# Antenna_Board_v5_0.net
KiCad netlist of a schematic drawn in EAGLE
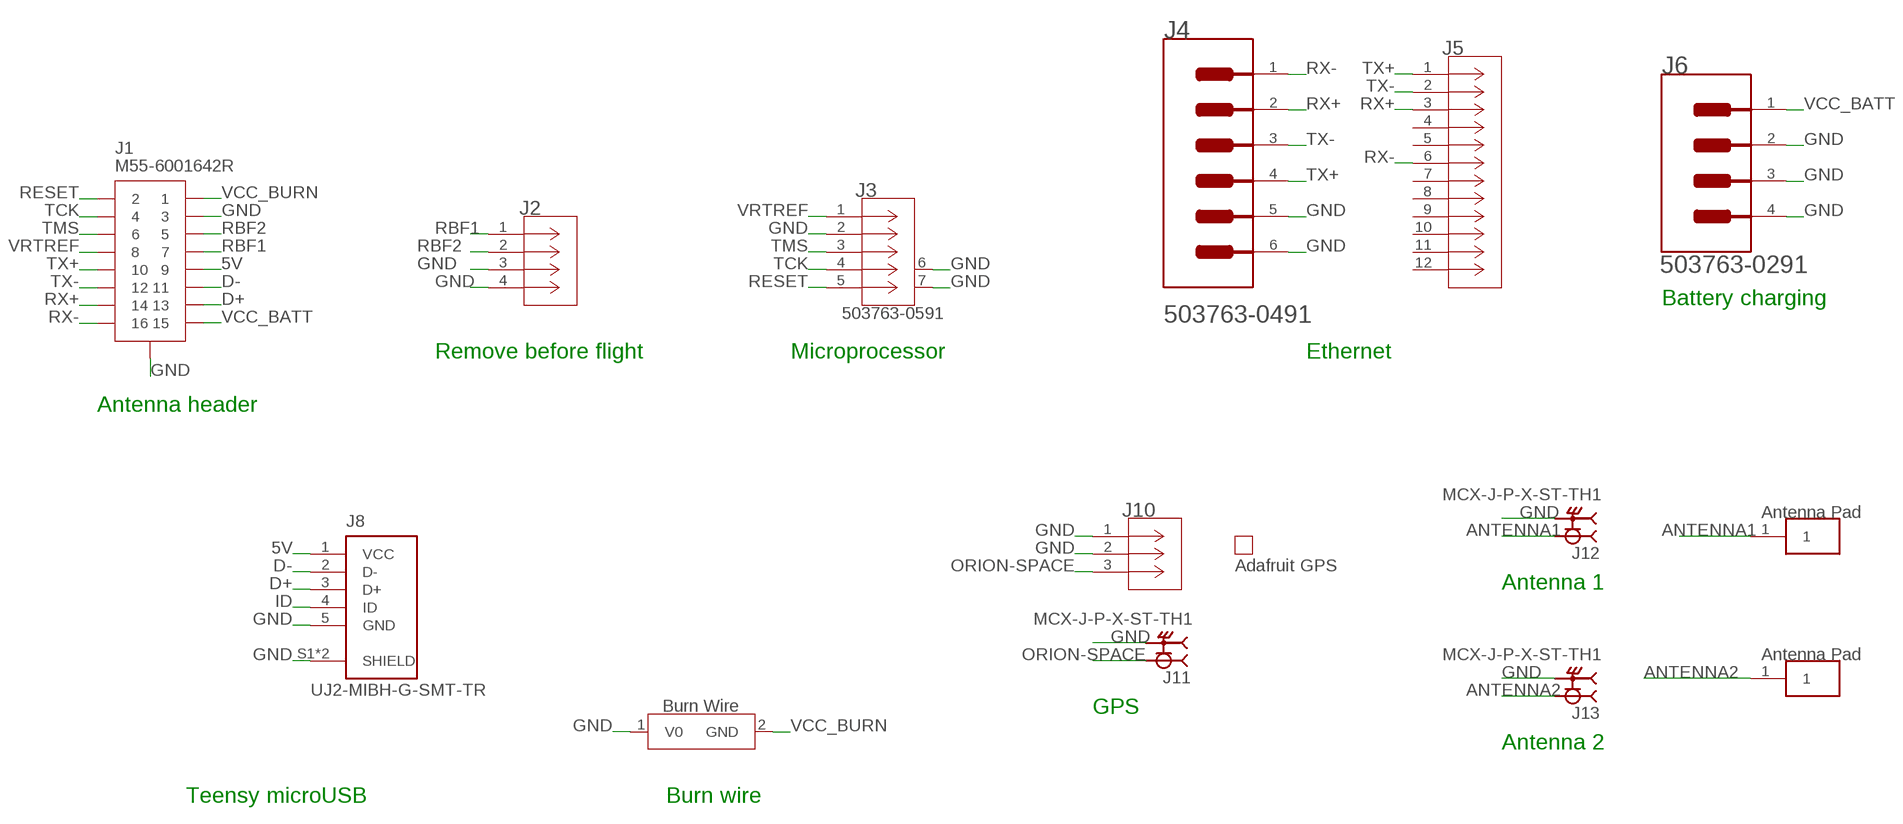
[diagram p0: schematic, sheet 1]

(export (version "E")
  (design (tool "Eeschema 10.0.6"))
  (components
    (comp (ref "GPS")
      (value "PA1010D")
      (footprint "eagle-import:PA1010D")
      (libsource (lib "eagle-import") (part "PA1010D"))
    )
    (comp (ref "J1")
      (value "M55-6001642R")
      (footprint "eagle-import:CONN_M55-6001642R_HRW")
      (fields (field (name "COPYRIGHT") "Copyright (C) 2021 Ultra Librarian. All rights reserved."))
      (libsource (lib "eagle-import") (part "M55-6001642R"))
    )
    (comp (ref "J2")
      (value "5037630291")
      (footprint "eagle-import:CON_5037630291")
      (fields (field (name "COPYRIGHT") "Copyright (C) 2018 Accelerated Designs. All rights reserved"))
      (libsource (lib "eagle-import") (part "5037630291"))
    )
    (comp (ref "J3")
      (value "503763-0591")
      (footprint "eagle-import:CONN_5037630591_MOL")
      (fields (field (name "COPYRIGHT") "Copyright (C) 2018 Accelerated Designs. All rights reserved"))
      (libsource (lib "eagle-import") (part "503763-0591"))
    )
    (comp (ref "J4")
      (value "MOLEX_503763-0491MOLEX_503763-0491_0_0")
      (footprint "eagle-import:MOLEX_503763-0491_0")
      (fields
        (field (name "DIGIKEY_PART_NUMBER") "WM10655CT-ND")
        (field (name "MF") "Molex")
        (field (name "MOUSER_PART_NUMBER") "538-503763-0491")
      )
      (libsource (lib "eagle-import") (part "MOLEX_503763-0491MOLEX_503763-0491_0_0"))
    )
    (comp (ref "J5")
      (value "ARJM11C7-104-AB-EW2")
      (footprint "eagle-import:CONN_EW_ABR")
      (libsource (lib "eagle-import") (part "ARJM11C7-104-AB-EW2"))
    )
    (comp (ref "J6")
      (value "MOLEX_503763-0291MOLEX_503763-0291_0_0")
      (footprint "eagle-import:MOLEX_503763-0291_0")
      (fields
        (field (name "DIGIKEY_PART_NUMBER") "WM10654CT-ND")
        (field (name "MF") "Molex")
        (field (name "MOUSER_PART_NUMBER") "538-503763-0291")
      )
      (libsource (lib "eagle-import") (part "MOLEX_503763-0291MOLEX_503763-0291_0_0"))
    )
    (comp (ref "J8")
      (value "UJ2-MIBH-G-SMT-TR")
      (footprint "eagle-import:CUI_UJ2-MIBH-G-SMT-TR")
      (fields
        (field (name "DIGI-KEY_PART_NUMBER") "2223-UJ2-MIBH-G-SMT-TRCT-ND")
        (field (name "MF") "CUI Devices")
      )
      (libsource (lib "eagle-import") (part "UJ2-MIBH-G-SMT-TR"))
    )
    (comp (ref "J10")
      (value "U.FL-R-SMT-1(01)")
      (footprint "eagle-import:CONN_-SMT-1(01)")
      (fields (field (name "COPYRIGHT") "Copyright (C) 2018 Accelerated Designs. All rights reserved"))
      (libsource (lib "eagle-import") (part "U.FL-R-SMT-1(01)"))
    )
    (comp (ref "J11")
      (value "MCX-J-P-X-ST-TH1")
      (footprint "eagle-import:SAMTEC_MCX-J-P-X-ST-TH1")
      (fields
        (field (name "DIGI-KEY_PART_NUMBER") "SAM8944-ND")
        (field (name "MF") "Samtec")
        (field (name "MP") "MCX-J-P-H-ST-TH1")
      )
      (libsource (lib "eagle-import") (part "MCX-J-P-X-ST-TH1"))
    )
    (comp (ref "J12")
      (value "MCX-J-P-X-ST-TH1")
      (footprint "eagle-import:SAMTEC_MCX-J-P-X-ST-TH1")
      (fields
        (field (name "DIGI-KEY_PART_NUMBER") "SAM8944-ND")
        (field (name "MF") "Samtec")
        (field (name "MP") "MCX-J-P-H-ST-TH1")
      )
      (libsource (lib "eagle-import") (part "MCX-J-P-X-ST-TH1"))
    )
    (comp (ref "J13")
      (value "MCX-J-P-X-ST-TH1")
      (footprint "eagle-import:SAMTEC_MCX-J-P-X-ST-TH1")
      (fields
        (field (name "DIGI-KEY_PART_NUMBER") "SAM8944-ND")
        (field (name "MF") "Samtec")
        (field (name "MP") "MCX-J-P-H-ST-TH1")
      )
      (libsource (lib "eagle-import") (part "MCX-J-P-X-ST-TH1"))
    )
    (comp (ref "U$1")
      (value "ANTENNA_PAD")
      (footprint "eagle-import:ANTENNA_PAD")
      (libsource (lib "eagle-import") (part "ANTENNA_PAD"))
    )
    (comp (ref "U$2")
      (value "ANTENNA_PAD")
      (footprint "eagle-import:ANTENNA_PAD")
      (libsource (lib "eagle-import") (part "ANTENNA_PAD"))
    )
    (comp (ref "U$3")
      (value "BURNWIRE")
      (footprint "eagle-import:BURNWIRE")
      (libsource (lib "eagle-import") (part "BURNWIRE"))
    )
  )
  (nets
    (net (code "1") (name "/5V") (class "Default")
      (node (ref "J1") (pin "9") (pinfunction "9_9") (pintype "passive"))
      (node (ref "J8") (pin "1") (pinfunction "VCC_1") (pintype "power_in"))
    )
    (net (code "2") (name "/ANTENNA1") (class "Default")
      (node (ref "J12") (pin "1") (pinfunction "1_1") (pintype "passive"))
      (node (ref "U$2") (pin "1") (pinfunction "1_1") (pintype "bidirectional"))
    )
    (net (code "3") (name "/ANTENNA2") (class "Default")
      (node (ref "J13") (pin "1") (pinfunction "1_1") (pintype "passive"))
      (node (ref "U$1") (pin "1") (pinfunction "1_1") (pintype "bidirectional"))
    )
    (net (code "4") (name "/D+") (class "Default")
      (node (ref "J1") (pin "13") (pinfunction "13_13") (pintype "passive"))
      (node (ref "J8") (pin "3") (pinfunction "D+_3") (pintype "bidirectional"))
    )
    (net (code "5") (name "/D-") (class "Default")
      (node (ref "J1") (pin "11") (pinfunction "11_11") (pintype "passive"))
      (node (ref "J8") (pin "2") (pinfunction "D-_2") (pintype "bidirectional"))
    )
    (net (code "6") (name "/GND") (class "Default")
      (node (ref "J1") (pin "19") (pinfunction "GND_19") (pintype "passive"))
      (node (ref "J1") (pin "20") (pinfunction "GND_20") (pintype "passive"))
      (node (ref "J1") (pin "21") (pinfunction "GND_21") (pintype "passive"))
      (node (ref "J1") (pin "22") (pinfunction "GND_22") (pintype "passive"))
      (node (ref "J1") (pin "3") (pinfunction "3_3") (pintype "passive"))
      (node (ref "J10") (pin "1") (pinfunction "1_1") (pintype "passive"))
      (node (ref "J10") (pin "2") (pinfunction "2_2") (pintype "passive"))
      (node (ref "J11") (pin "S1") (pinfunction "2_S1") (pintype "passive"))
      (node (ref "J11") (pin "S2") (pinfunction "2_S2") (pintype "passive"))
      (node (ref "J11") (pin "S3") (pinfunction "2_S3") (pintype "passive"))
      (node (ref "J11") (pin "S4") (pinfunction "2_S4") (pintype "passive"))
      (node (ref "J12") (pin "S1") (pinfunction "2_S1") (pintype "passive"))
      (node (ref "J12") (pin "S2") (pinfunction "2_S2") (pintype "passive"))
      (node (ref "J12") (pin "S3") (pinfunction "2_S3") (pintype "passive"))
      (node (ref "J12") (pin "S4") (pinfunction "2_S4") (pintype "passive"))
      (node (ref "J13") (pin "S1") (pinfunction "2_S1") (pintype "passive"))
      (node (ref "J13") (pin "S2") (pinfunction "2_S2") (pintype "passive"))
      (node (ref "J13") (pin "S3") (pinfunction "2_S3") (pintype "passive"))
      (node (ref "J13") (pin "S4") (pinfunction "2_S4") (pintype "passive"))
      (node (ref "J2") (pin "3") (pinfunction "3_3") (pintype "passive"))
      (node (ref "J2") (pin "4") (pinfunction "4_4") (pintype "passive"))
      (node (ref "J3") (pin "2") (pinfunction "2_2") (pintype "passive"))
      (node (ref "J3") (pin "6") (pinfunction "6_6") (pintype "bidirectional"))
      (node (ref "J3") (pin "7") (pinfunction "7_7") (pintype "bidirectional"))
      (node (ref "J4") (pin "5") (pinfunction "MNT_1_5") (pintype "passive"))
      (node (ref "J4") (pin "6") (pinfunction "MNT_2_6") (pintype "passive"))
      (node (ref "J6") (pin "2") (pinfunction "2_2") (pintype "bidirectional"))
      (node (ref "J6") (pin "3") (pinfunction "MNT_1_3") (pintype "bidirectional"))
      (node (ref "J6") (pin "4") (pinfunction "MNT_2_4") (pintype "bidirectional"))
      (node (ref "J8") (pin "5") (pinfunction "GND_5") (pintype "power_in"))
      (node (ref "J8") (pin "S1") (pinfunction "SHIELD_S1") (pintype "passive"))
      (node (ref "J8") (pin "S2") (pinfunction "SHIELD_S2") (pintype "passive"))
      (node (ref "U$3") (pin "1") (pinfunction "V0_1") (pintype "bidirectional"))
    )
    (net (code "7") (name "/ID") (class "Default")
      (node (ref "J8") (pin "4") (pinfunction "ID_4") (pintype "bidirectional"))
    )
    (net (code "8") (name "/ORION-SPACE") (class "Default")
      (node (ref "J10") (pin "3") (pinfunction "3_3") (pintype "passive"))
      (node (ref "J11") (pin "1") (pinfunction "1_1") (pintype "passive"))
    )
    (net (code "9") (name "/RBF1") (class "Default")
      (node (ref "J1") (pin "7") (pinfunction "7_7") (pintype "passive"))
      (node (ref "J2") (pin "1") (pinfunction "1_1") (pintype "passive"))
    )
    (net (code "10") (name "/RBF2") (class "Default")
      (node (ref "J1") (pin "5") (pinfunction "5_5") (pintype "passive"))
      (node (ref "J2") (pin "2") (pinfunction "2_2") (pintype "passive"))
    )
    (net (code "11") (name "/RESET") (class "Default")
      (node (ref "J1") (pin "2") (pinfunction "2_2") (pintype "passive"))
      (node (ref "J3") (pin "5") (pinfunction "5_5") (pintype "passive"))
    )
    (net (code "12") (name "/RX+") (class "Default")
      (node (ref "J1") (pin "14") (pinfunction "14_14") (pintype "passive"))
      (node (ref "J4") (pin "2") (pinfunction "2_2") (pintype "passive"))
      (node (ref "J5") (pin "3") (pinfunction "3_3") (pintype "passive"))
    )
    (net (code "13") (name "/RX-") (class "Default")
      (node (ref "J1") (pin "16") (pinfunction "16_16") (pintype "passive"))
      (node (ref "J4") (pin "1") (pinfunction "1_1") (pintype "passive"))
      (node (ref "J5") (pin "6") (pinfunction "6_6") (pintype "passive"))
    )
    (net (code "14") (name "/TCK") (class "Default")
      (node (ref "J1") (pin "4") (pinfunction "4_4") (pintype "passive"))
      (node (ref "J3") (pin "4") (pinfunction "4_4") (pintype "passive"))
    )
    (net (code "15") (name "/TMS") (class "Default")
      (node (ref "J1") (pin "6") (pinfunction "6_6") (pintype "passive"))
      (node (ref "J3") (pin "3") (pinfunction "3_3") (pintype "passive"))
    )
    (net (code "16") (name "/TX+") (class "Default")
      (node (ref "J1") (pin "10") (pinfunction "10_10") (pintype "passive"))
      (node (ref "J4") (pin "4") (pinfunction "4_4") (pintype "passive"))
      (node (ref "J5") (pin "1") (pinfunction "1_1") (pintype "passive"))
    )
    (net (code "17") (name "/TX-") (class "Default")
      (node (ref "J1") (pin "12") (pinfunction "12_12") (pintype "passive"))
      (node (ref "J4") (pin "3") (pinfunction "3_3") (pintype "passive"))
      (node (ref "J5") (pin "2") (pinfunction "2_2") (pintype "passive"))
    )
    (net (code "18") (name "/VCC_BATT") (class "Default")
      (node (ref "J1") (pin "15") (pinfunction "15_15") (pintype "passive"))
      (node (ref "J6") (pin "1") (pinfunction "1_1") (pintype "bidirectional"))
    )
    (net (code "19") (name "/VCC_BURN") (class "Default")
      (node (ref "J1") (pin "1") (pinfunction "1_1") (pintype "passive"))
      (node (ref "U$3") (pin "2") (pinfunction "GND_2") (pintype "bidirectional"))
    )
    (net (code "20") (name "/VRTREF") (class "Default")
      (node (ref "J1") (pin "8") (pinfunction "8_8") (pintype "passive"))
      (node (ref "J3") (pin "1") (pinfunction "1_1") (pintype "passive"))
    )
    (net (code "21") (name "unconnected-(J5-Pad4)") (class "Default")
      (node (ref "J5") (pin "4") (pinfunction "4_4") (pintype "passive"))
    )
    (net (code "22") (name "unconnected-(J5-Pad5)") (class "Default")
      (node (ref "J5") (pin "5") (pinfunction "5_5") (pintype "passive"))
    )
    (net (code "23") (name "unconnected-(J5-Pad7)") (class "Default")
      (node (ref "J5") (pin "7") (pinfunction "7_7") (pintype "passive"))
    )
    (net (code "24") (name "unconnected-(J5-Pad8)") (class "Default")
      (node (ref "J5") (pin "8") (pinfunction "8_8") (pintype "passive"))
    )
    (net (code "25") (name "unconnected-(J5-Pad9)") (class "Default")
      (node (ref "J5") (pin "9") (pinfunction "9_9") (pintype "passive"))
    )
    (net (code "26") (name "unconnected-(J5-Pad10)") (class "Default")
      (node (ref "J5") (pin "10") (pinfunction "10_10") (pintype "passive"))
    )
    (net (code "27") (name "unconnected-(J5-Pad11)") (class "Default")
      (node (ref "J5") (pin "11") (pinfunction "11_11") (pintype "passive"))
    )
    (net (code "28") (name "unconnected-(J5-Pad12)") (class "Default")
      (node (ref "J5") (pin "12") (pinfunction "12_12") (pintype "passive"))
    )
  )
)
